# MRF49XAmboard.net
KiCad netlist of a schematic drawn in Altium Designer
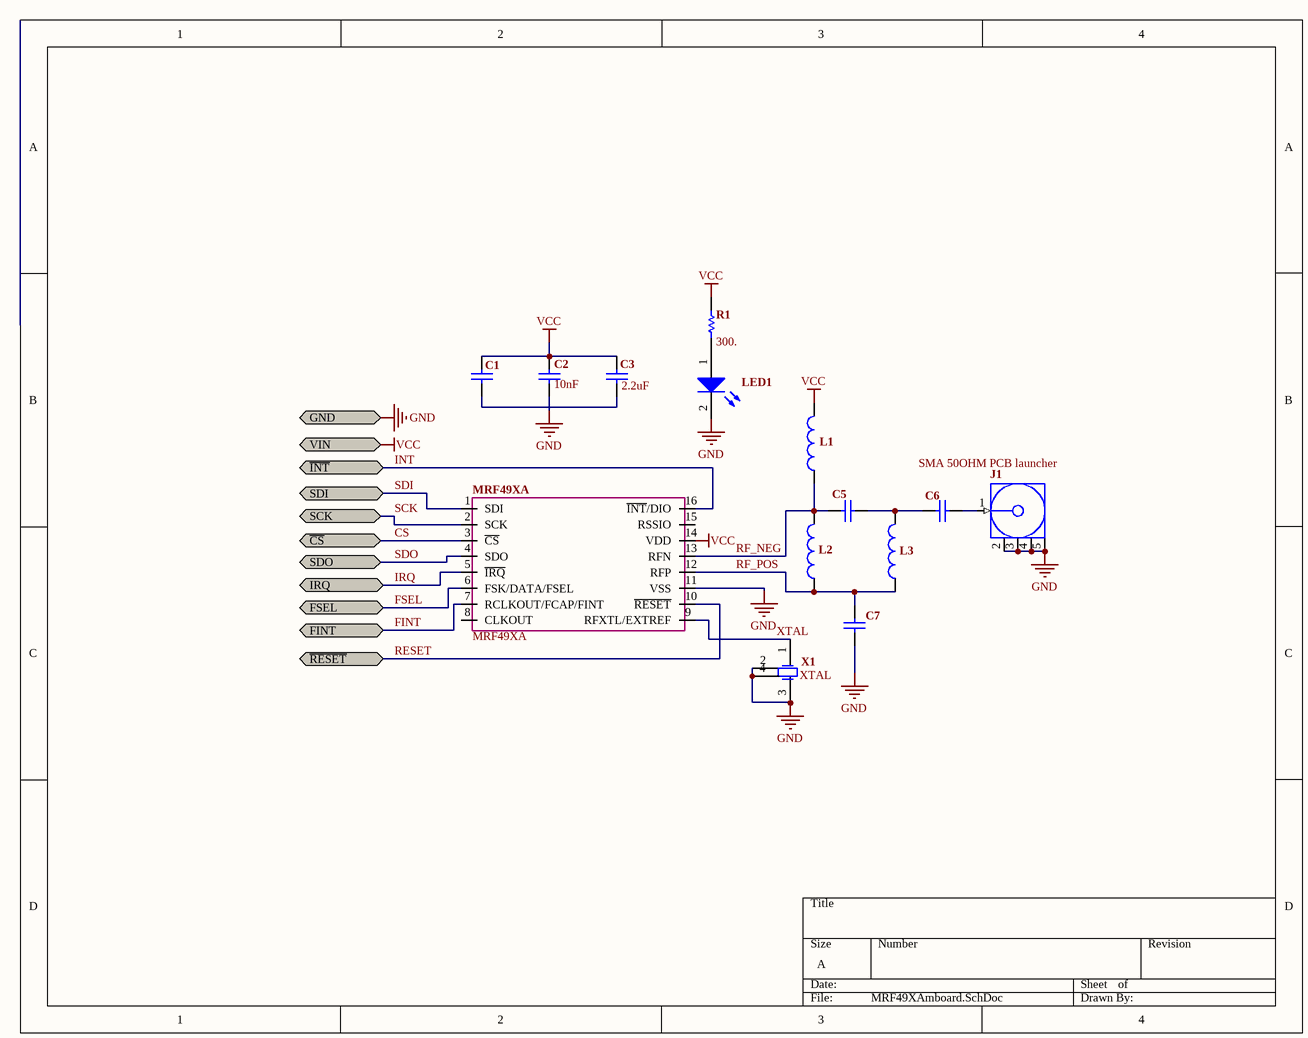
[diagram p0: MRF49XAmboard.SchDoc]

(export (version "E")
  (design (tool "Eeschema 10.0.6"))
  (components
    (comp (ref "C1")
      (value "Cap")
      (footprint "1608[0603]")
      (description "Capacitor")
      (fields (field (name "PUBLISHER") "Altium Limited"))
      (libsource (lib "Miscellaneous Devices") (part "Cap"))
    )
    (comp (ref "C2")
      (value "10nF")
      (footprint "1608[0603]")
      (description "Capacitor")
      (fields (field (name "Comment") "Cap") (field (name "PUBLISHER") "Altium Limited"))
      (libsource (lib "Miscellaneous Devices") (part "Cap"))
    )
    (comp (ref "C3")
      (value "2.2uF")
      (footprint "CAPC3216N")
      (description "Capacitor")
      (fields (field (name "Comment") "Cap") (field (name "PUBLISHER") "Altium Limited"))
      (libsource (lib "agus_lib") (part "Cap"))
    )
    (comp (ref "C5")
      (value "Cap")
      (footprint "1608[0603]")
      (description "Capacitor")
      (fields (field (name "PUBLISHER") "Altium Limited"))
      (libsource (lib "Miscellaneous Devices") (part "Cap"))
    )
    (comp (ref "C6")
      (value "Cap")
      (footprint "1608[0603]")
      (description "Capacitor")
      (fields (field (name "PUBLISHER") "Altium Limited"))
      (libsource (lib "Miscellaneous Devices") (part "Cap"))
    )
    (comp (ref "C7")
      (value "Cap")
      (footprint "1608[0603]")
      (description "Capacitor")
      (fields (field (name "PUBLISHER") "Altium Limited"))
      (libsource (lib "Miscellaneous Devices") (part "Cap"))
    )
    (comp (ref "J1")
      (value "SMA 50OHM PCB launcher")
      (footprint "SMA PCB LAUNCHER")
      (description "SMA RF Coaxial PCB Connector, SM, Vertical Mount Socket, 50 Ohm Impedance")
      (fields (field (name "PUBLISHER") "Altium Limited"))
      (libsource (lib "agus_lib") (part "SMA 50OHM PCB launcher"))
    )
    (comp (ref "L1")
      (value "L")
      (footprint "1608[0603]")
      (description "Inductor")
      (fields
        (field (name "MANUFACTURER") "Generic Components")
        (field (name "PUBLISHER") "Altium Hobart Technology Centre")
      )
      (libsource (lib "LSI") (part "L"))
    )
    (comp (ref "L2")
      (value "L")
      (footprint "1608[0603]")
      (description "Inductor")
      (fields
        (field (name "MANUFACTURER") "Generic Components")
        (field (name "PUBLISHER") "Altium Hobart Technology Centre")
      )
      (libsource (lib "LSI") (part "L"))
    )
    (comp (ref "L3")
      (value "L")
      (footprint "1608[0603]")
      (description "Inductor")
      (fields
        (field (name "MANUFACTURER") "Generic Components")
        (field (name "PUBLISHER") "Altium Hobart Technology Centre")
      )
      (libsource (lib "LSI") (part "L"))
    )
    (comp (ref "LED1")
      (value "LED_SMD_Hg")
      (footprint "1608[0603]")
      (description "Typical BLUE SiC LED")
      (fields
        (field (name "MANUFACTURER") "Generic Components")
        (field (name "PUBLISHER") "Altium Hobart Technology Centre")
      )
      (libsource (lib "LSI") (part "LED_SMD_Hg"))
    )
    (comp (ref "MRF49XA")
      (value "MRF49XA")
      (footprint "MRF49XA")
      (description "Sub-GHz RF transceiver supporting the 433/868/915MHz ISM frequency band")
      (libsource (lib "agus_lib") (part "MRF49XA"))
    )
    (comp (ref "R1")
      (value "300.")
      (footprint "1608[0603]")
      (description "Resistor")
      (fields (field (name "Comment") "Res1") (field (name "PUBLISHER") "Altium Limited"))
      (libsource (lib "Miscellaneous Devices") (part "Res1"))
    )
    (comp (ref "X1")
      (value "XTAL")
      (footprint "XTC CRYSTAL")
      (description "Crystal Oscillator")
      (fields (field (name "PUBLISHER") "Altium Limited"))
      (libsource (lib "agus_lib") (part "XTAL"))
    )
  )
  (nets
    (net (code "1") (name "/CS") (class "Default")
      (node (ref "MRF49XA") (pin "3") (pinfunction "~{CS}_3") (pintype "passive"))
    )
    (net (code "2") (name "/FINT") (class "Default")
      (node (ref "MRF49XA") (pin "7") (pinfunction "RCLKOUT/FCAP/FINT_7") (pintype "passive"))
    )
    (net (code "3") (name "/FSEL") (class "Default")
      (node (ref "MRF49XA") (pin "6") (pinfunction "FSK/DATA/FSEL_6") (pintype "passive"))
    )
    (net (code "4") (name "/INT") (class "Default")
      (node (ref "MRF49XA") (pin "16") (pinfunction "~{INT}/DIO_16") (pintype "passive"))
    )
    (net (code "5") (name "/IRQ") (class "Default")
      (node (ref "MRF49XA") (pin "5") (pinfunction "~{IRQ}_5") (pintype "passive"))
    )
    (net (code "6") (name "/RESET") (class "Default")
      (node (ref "MRF49XA") (pin "10") (pinfunction "~{RESET}_10") (pintype "passive"))
    )
    (net (code "7") (name "/RF_NEG") (class "Default")
      (node (ref "C5") (pin "2") (pinfunction "2_2") (pintype "passive"))
      (node (ref "L1") (pin "1") (pinfunction "1_1") (pintype "passive"))
      (node (ref "L2") (pin "2") (pinfunction "2_2") (pintype "passive"))
      (node (ref "MRF49XA") (pin "13") (pinfunction "RFN_13") (pintype "passive"))
    )
    (net (code "8") (name "/RF_POS") (class "Default")
      (node (ref "C7") (pin "2") (pinfunction "2_2") (pintype "passive"))
      (node (ref "L2") (pin "1") (pinfunction "1_1") (pintype "passive"))
      (node (ref "L3") (pin "1") (pinfunction "1_1") (pintype "passive"))
      (node (ref "MRF49XA") (pin "12") (pinfunction "RFP_12") (pintype "passive"))
    )
    (net (code "9") (name "/SCK") (class "Default")
      (node (ref "MRF49XA") (pin "2") (pinfunction "SCK_2") (pintype "passive"))
    )
    (net (code "10") (name "/SDI") (class "Default")
      (node (ref "MRF49XA") (pin "1") (pinfunction "SDI_1") (pintype "passive"))
    )
    (net (code "11") (name "/SDO") (class "Default")
      (node (ref "MRF49XA") (pin "4") (pinfunction "SDO_4") (pintype "passive"))
    )
    (net (code "12") (name "/XTAL") (class "Default")
      (node (ref "MRF49XA") (pin "9") (pinfunction "RFXTL/EXTREF_9") (pintype "passive"))
      (node (ref "X1") (pin "1") (pinfunction "OSC1_1") (pintype "passive"))
    )
    (net (code "13") (name "GND") (class "Default")
      (node (ref "C2") (pin "1") (pinfunction "1_1") (pintype "passive"))
      (node (ref "C7") (pin "1") (pinfunction "1_1") (pintype "passive"))
      (node (ref "J1") (pin "2") (pinfunction "GND_2") (pintype "power_in"))
      (node (ref "J1") (pin "3") (pinfunction "GND_3") (pintype "power_in"))
      (node (ref "J1") (pin "4") (pinfunction "GND_4") (pintype "power_in"))
      (node (ref "J1") (pin "5") (pinfunction "GND_5") (pintype "power_in"))
      (node (ref "LED1") (pin "2") (pinfunction "K_2") (pintype "passive"))
      (node (ref "MRF49XA") (pin "11") (pinfunction "VSS_11") (pintype "passive"))
      (node (ref "X1") (pin "2") (pinfunction "GND_2") (pintype "passive"))
      (node (ref "X1") (pin "3") (pinfunction "OSC2_3") (pintype "passive"))
      (node (ref "X1") (pin "4") (pinfunction "GND_4") (pintype "passive"))
    )
    (net (code "14") (name "Net-(C1-Pad1)") (class "Default")
      (node (ref "C1") (pin "1") (pinfunction "1_1") (pintype "passive"))
      (node (ref "C3") (pin "1") (pinfunction "1_1") (pintype "passive"))
    )
    (net (code "15") (name "Net-(C5-Pad1)") (class "Default")
      (node (ref "C5") (pin "1") (pinfunction "1_1") (pintype "passive"))
      (node (ref "C6") (pin "2") (pinfunction "2_2") (pintype "passive"))
      (node (ref "L3") (pin "2") (pinfunction "2_2") (pintype "passive"))
    )
    (net (code "16") (name "Net-(J1-Signal)") (class "Default")
      (node (ref "C6") (pin "1") (pinfunction "1_1") (pintype "passive"))
      (node (ref "J1") (pin "1") (pinfunction "Signal_1") (pintype "input"))
    )
    (net (code "17") (name "Net-(LED1-A)") (class "Default")
      (node (ref "LED1") (pin "1") (pinfunction "A_1") (pintype "passive"))
      (node (ref "R1") (pin "1") (pinfunction "1_1") (pintype "passive"))
    )
    (net (code "18") (name "VCC") (class "Default")
      (node (ref "C1") (pin "2") (pinfunction "2_2") (pintype "passive"))
      (node (ref "C2") (pin "2") (pinfunction "2_2") (pintype "passive"))
      (node (ref "C3") (pin "2") (pinfunction "2_2") (pintype "passive"))
      (node (ref "L1") (pin "2") (pinfunction "2_2") (pintype "passive"))
      (node (ref "MRF49XA") (pin "14") (pinfunction "VDD_14") (pintype "passive"))
      (node (ref "R1") (pin "2") (pinfunction "2_2") (pintype "passive"))
    )
    (net (code "19") (name "unconnected-(MRF49XA-CLKOUT-Pad8)") (class "Default")
      (node (ref "MRF49XA") (pin "8") (pinfunction "CLKOUT_8") (pintype "passive"))
    )
    (net (code "20") (name "unconnected-(MRF49XA-RSSIO-Pad15)") (class "Default")
      (node (ref "MRF49XA") (pin "15") (pinfunction "RSSIO_15") (pintype "passive"))
    )
  )
)
